# Power_Supply.net
KiCad netlist of a schematic drawn in Altium Designer
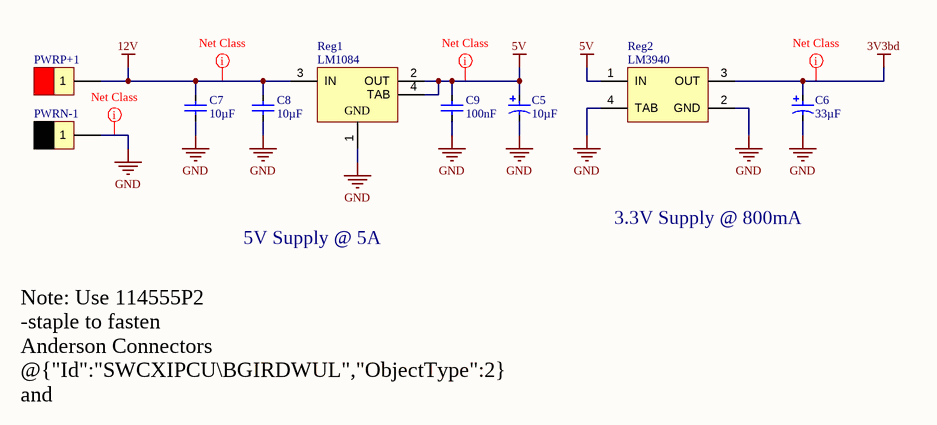
[diagram p0:  Power Supply.SchDoc]

(export (version "E")
  (design (tool "Eeschema 10.0.6"))
  (components
    (comp (ref "C5")
      (value "10µF")
      (footprint "AVX-TPSB106K020R1000_L")
      (fields (field (name "Comment") "TPSB106K020R1000"))
      (libsource (lib "Advanced] Training Course - A365") (part "CAP_Polar Generic"))
    )
    (comp (ref "C6")
      (value "33µF")
      (footprint "FP-TAJY-MFG")
      (fields (field (name "Comment") "TAJY336K020RNJ"))
      (libsource (lib "Advanced] Training Course - A365") (part "CAP_Polar Generic"))
    )
    (comp (ref "C7")
      (value "10µF")
      (footprint "CAPC2013X135X45ML10T25")
      (fields (field (name "TOLERANCE") "10%") (field (name "Comment") "CAP_Murata"))
      (libsource (lib "Advanced] Training Course - A365") (part "CAP_Murata"))
    )
    (comp (ref "C8")
      (value "10µF")
      (footprint "CAPC2013X135X45ML10T25")
      (fields (field (name "TOLERANCE") "10%") (field (name "Comment") "CAP_Murata"))
      (libsource (lib "Advanced] Training Course - A365") (part "CAP_Murata"))
    )
    (comp (ref "C9")
      (value "100nF")
      (footprint "0603C_L")
      (fields (field (name "Comment") "Cap100nF_50V_0603"))
      (libsource (lib "Advanced] Training Course - A365") (part "CAP General"))
    )
    (comp (ref "PWRN-1")
      (value "Anderson-1Pin BLK_PCB_RHT")
      (footprint "Anderson_BLK_RHT_BOT")
      (description "Connector Accessory, Contact, Copper Alloy")
      (libsource (lib "Advanced] Training Course - A365") (part "Anderson-1Pin BLK_PCB_RHT"))
    )
    (comp (ref "PWRP+1")
      (value "Anderson-1Pin RED_PCB_RHT")
      (footprint "Anderson_RED_RHT_BOT")
      (description "Connector Accessory, Contact, Copper Alloy")
      (libsource (lib "TC - Altium Essentials Course A365 13") (part "Anderson-1Pin RED_PCB_RHT"))
    )
    (comp (ref "Reg1")
      (value "LM1084")
      (footprint "KTT0003B_L")
      (description "5A Low Dropout Positive Regulators, 3-pin TO-263, Pb-Free")
      (fields
        (field (name "MANUFACTURER") "Texas Instruments")
        (field (name "PARTNUMBER") "LM1084IS-5.0/NOPB")
        (field (name "SOURCE") "WCT.SchLib")
        (field (name "AVAILABLE PREVIEW IMAGES") "2D")
      )
      (libsource (lib "Advanced] Training Course - A365") (part "LM1084"))
    )
    (comp (ref "Reg2")
      (value "LM3940")
      (footprint "SOT223")
      (description "1A Low Dropout Regulator for 5V to 3.3V Conversion, 4-pin SOT-223, Pb-Free")
      (fields
        (field (name "MANUFACTURER") "Texas Instruments")
        (field (name "MANUFACTURER PART NUMBER") "LM3940IMP-3.3/NOPB")
        (field (name "SOURCE") "WCT.SchLib")
      )
      (libsource (lib "Advanced] Training Course - A365") (part "LM3940"))
    )
  )
  (nets
    (net (code "1") (name "3V3bd") (class "Default")
      (node (ref "C6") (pin "2") (pinfunction "2_2") (pintype "passive"))
      (node (ref "Reg2") (pin "3") (pinfunction "OUT_3") (pintype "power_in"))
    )
    (net (code "2") (name "5V") (class "Default")
      (node (ref "C5") (pin "2") (pinfunction "2_2") (pintype "passive"))
      (node (ref "C9") (pin "2") (pinfunction "2_2") (pintype "passive"))
      (node (ref "Reg1") (pin "2") (pinfunction "OUT_2") (pintype "power_in"))
      (node (ref "Reg1") (pin "4") (pinfunction "TAB_4") (pintype "power_in"))
      (node (ref "Reg2") (pin "1") (pinfunction "IN_1") (pintype "power_in"))
    )
    (net (code "3") (name "12V") (class "Default")
      (node (ref "C7") (pin "2") (pinfunction "2_2") (pintype "passive"))
      (node (ref "C8") (pin "2") (pinfunction "2_2") (pintype "passive"))
      (node (ref "PWRP+1") (pin "1") (pinfunction "1_1") (pintype "passive"))
      (node (ref "Reg1") (pin "3") (pinfunction "IN_3") (pintype "power_in"))
    )
    (net (code "4") (name "GND") (class "Default")
      (node (ref "C5") (pin "1") (pinfunction "1_1") (pintype "passive"))
      (node (ref "C6") (pin "1") (pinfunction "1_1") (pintype "passive"))
      (node (ref "C7") (pin "1") (pinfunction "1_1") (pintype "passive"))
      (node (ref "C8") (pin "1") (pinfunction "1_1") (pintype "passive"))
      (node (ref "C9") (pin "1") (pinfunction "1_1") (pintype "passive"))
      (node (ref "PWRN-1") (pin "1") (pinfunction "1_1") (pintype "passive"))
      (node (ref "Reg1") (pin "1") (pinfunction "GND_1") (pintype "power_in"))
      (node (ref "Reg2") (pin "2") (pinfunction "GND_2") (pintype "power_in"))
      (node (ref "Reg2") (pin "4") (pinfunction "TAB_4") (pintype "power_in"))
    )
  )
)
